# advsensor.net
KiCad netlist of a schematic drawn in Altium Designer
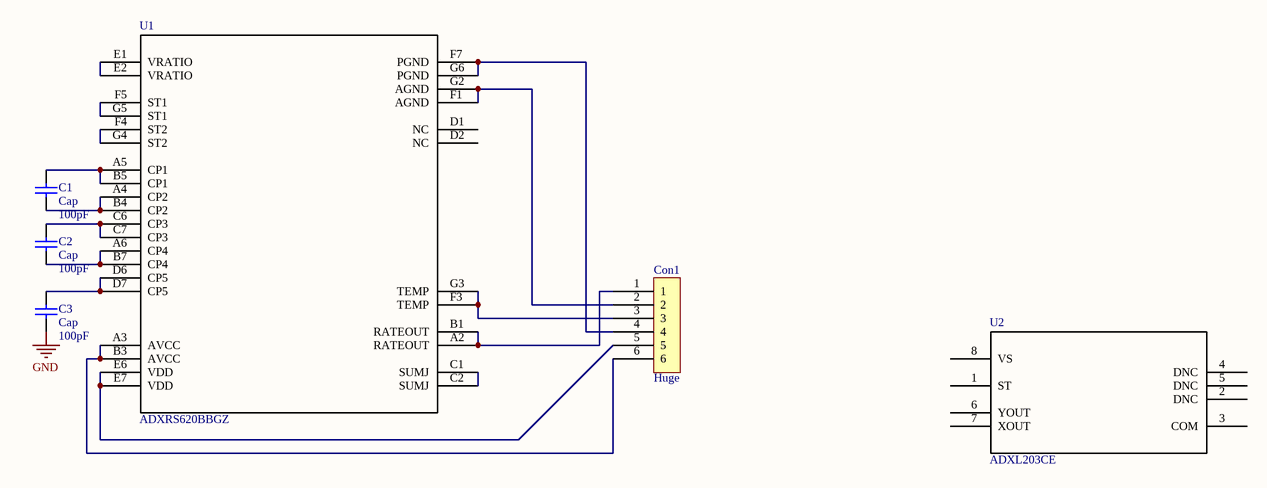
[diagram p0: advsensor.SchDoc]

(export (version "E")
  (design (tool "Eeschema 10.0.6"))
  (components
    (comp (ref "C1")
      (value "Cap")
      (footprint "0805")
      (description "Capacitor")
      (fields (field (name "ALTIUM_VALUE") "100pF") (field (name "PUBLISHER") "Altium Limited"))
      (libsource (lib "Miscellaneous Devices") (part "Cap"))
    )
    (comp (ref "C2")
      (value "Cap")
      (footprint "0805")
      (description "Capacitor")
      (fields (field (name "ALTIUM_VALUE") "100pF") (field (name "PUBLISHER") "Altium Limited"))
      (libsource (lib "Miscellaneous Devices") (part "Cap"))
    )
    (comp (ref "C3")
      (value "Cap")
      (footprint "0805")
      (description "Capacitor")
      (fields (field (name "ALTIUM_VALUE") "100pF") (field (name "PUBLISHER") "Altium Limited"))
      (libsource (lib "Miscellaneous Devices") (part "Cap"))
    )
    (comp (ref "Con1") (value "Huge") (footprint "HUGE2") (libsource (lib "complements") (part "Huge")))
    (comp (ref "U1")
      (value "ADXRS620BBGZ")
      (footprint "BG_32_3")
      (description "Imported")
      (fields (field (name "MANUFACTURER_PART_NUMBER") "ADXRS613BBGZ"))
      (libsource (lib "complements") (part "ADXRS620BBGZ"))
    )
    (comp (ref "U2")
      (value "ADXL203CE")
      (footprint "ADXL203")
      (description "Imported")
      (libsource (lib "complements") (part "ADXL203CE"))
    )
  )
  (nets
    (net (code "1") (name "GND") (class "Default")
      (node (ref "C3") (pin "1") (pinfunction "1_1") (pintype "passive"))
    )
    (net (code "2") (name "Net-(C1-Pad1)") (class "Default")
      (node (ref "C1") (pin "1") (pinfunction "1_1") (pintype "passive"))
      (node (ref "U1") (pin "A4") (pinfunction "CP2_A4") (pintype "passive"))
      (node (ref "U1") (pin "B4") (pinfunction "CP2_B4") (pintype "passive"))
    )
    (net (code "3") (name "Net-(C1-Pad2)") (class "Default")
      (node (ref "C1") (pin "2") (pinfunction "2_2") (pintype "passive"))
      (node (ref "U1") (pin "A5") (pinfunction "CP1_A5") (pintype "passive"))
      (node (ref "U1") (pin "B5") (pinfunction "CP1_B5") (pintype "passive"))
    )
    (net (code "4") (name "Net-(C2-Pad1)") (class "Default")
      (node (ref "C2") (pin "1") (pinfunction "1_1") (pintype "passive"))
      (node (ref "U1") (pin "A6") (pinfunction "CP4_A6") (pintype "passive"))
      (node (ref "U1") (pin "B7") (pinfunction "CP4_B7") (pintype "passive"))
    )
    (net (code "5") (name "Net-(C2-Pad2)") (class "Default")
      (node (ref "C2") (pin "2") (pinfunction "2_2") (pintype "passive"))
      (node (ref "U1") (pin "C6") (pinfunction "CP3_C6") (pintype "passive"))
      (node (ref "U1") (pin "C7") (pinfunction "CP3_C7") (pintype "passive"))
    )
    (net (code "6") (name "Net-(C3-Pad2)") (class "Default")
      (node (ref "C3") (pin "2") (pinfunction "2_2") (pintype "passive"))
      (node (ref "U1") (pin "D6") (pinfunction "CP5_D6") (pintype "passive"))
      (node (ref "U1") (pin "D7") (pinfunction "CP5_D7") (pintype "passive"))
    )
    (net (code "7") (name "Net-(Con1-Pad1)") (class "Default")
      (node (ref "Con1") (pin "1") (pinfunction "1_1") (pintype "passive"))
      (node (ref "U1") (pin "A2") (pinfunction "RATEOUT_A2") (pintype "passive"))
      (node (ref "U1") (pin "B1") (pinfunction "RATEOUT_B1") (pintype "passive"))
    )
    (net (code "8") (name "Net-(Con1-Pad2)") (class "Default")
      (node (ref "Con1") (pin "2") (pinfunction "2_2") (pintype "passive"))
      (node (ref "U1") (pin "F1") (pinfunction "AGND_F1") (pintype "passive"))
      (node (ref "U1") (pin "G2") (pinfunction "AGND_G2") (pintype "passive"))
    )
    (net (code "9") (name "Net-(Con1-Pad3)") (class "Default")
      (node (ref "Con1") (pin "3") (pinfunction "3_3") (pintype "passive"))
      (node (ref "U1") (pin "F3") (pinfunction "TEMP_F3") (pintype "passive"))
      (node (ref "U1") (pin "G3") (pinfunction "TEMP_G3") (pintype "passive"))
    )
    (net (code "10") (name "Net-(Con1-Pad4)") (class "Default")
      (node (ref "Con1") (pin "4") (pinfunction "4_4") (pintype "passive"))
      (node (ref "U1") (pin "F7") (pinfunction "PGND_F7") (pintype "passive"))
      (node (ref "U1") (pin "G6") (pinfunction "PGND_G6") (pintype "passive"))
    )
    (net (code "11") (name "Net-(Con1-Pad5)") (class "Default")
      (node (ref "Con1") (pin "5") (pinfunction "5_5") (pintype "passive"))
      (node (ref "U1") (pin "E6") (pinfunction "VDD_E6") (pintype "power_in"))
      (node (ref "U1") (pin "E7") (pinfunction "VDD_E7") (pintype "power_in"))
    )
    (net (code "12") (name "Net-(Con1-Pad6)") (class "Default")
      (node (ref "Con1") (pin "6") (pinfunction "6_6") (pintype "passive"))
      (node (ref "U1") (pin "A3") (pinfunction "AVCC_A3") (pintype "power_in"))
      (node (ref "U1") (pin "B3") (pinfunction "AVCC_B3") (pintype "power_in"))
    )
    (net (code "13") (name "Net-(U1-ST1-PadF5)") (class "Default")
      (node (ref "U1") (pin "F5") (pinfunction "ST1_F5") (pintype "passive"))
      (node (ref "U1") (pin "G5") (pinfunction "ST1_G5") (pintype "passive"))
    )
    (net (code "14") (name "Net-(U1-ST2-PadF4)") (class "Default")
      (node (ref "U1") (pin "F4") (pinfunction "ST2_F4") (pintype "passive"))
      (node (ref "U1") (pin "G4") (pinfunction "ST2_G4") (pintype "passive"))
    )
    (net (code "15") (name "Net-(U1-SUMJ-PadC1)") (class "Default")
      (node (ref "U1") (pin "C1") (pinfunction "SUMJ_C1") (pintype "passive"))
      (node (ref "U1") (pin "C2") (pinfunction "SUMJ_C2") (pintype "passive"))
    )
    (net (code "16") (name "Net-(U1-VRATIO-PadE1)") (class "Default")
      (node (ref "U1") (pin "E1") (pinfunction "VRATIO_E1") (pintype "power_in"))
      (node (ref "U1") (pin "E2") (pinfunction "VRATIO_E2") (pintype "power_in"))
    )
    (net (code "17") (name "unconnected-(U1-NC-PadD1)") (class "Default")
      (node (ref "U1") (pin "D1") (pinfunction "NC_D1") (pintype "passive"))
    )
    (net (code "18") (name "unconnected-(U1-NC-PadD2)") (class "Default")
      (node (ref "U1") (pin "D2") (pinfunction "NC_D2") (pintype "passive"))
    )
    (net (code "19") (name "unconnected-(U2-COM-Pad3)") (class "Default")
      (node (ref "U2") (pin "3") (pinfunction "COM_3") (pintype "passive"))
    )
    (net (code "20") (name "unconnected-(U2-DNC-Pad2)") (class "Default")
      (node (ref "U2") (pin "2") (pinfunction "DNC_2") (pintype "passive"))
    )
    (net (code "21") (name "unconnected-(U2-DNC-Pad4)") (class "Default")
      (node (ref "U2") (pin "4") (pinfunction "DNC_4") (pintype "passive"))
    )
    (net (code "22") (name "unconnected-(U2-DNC-Pad5)") (class "Default")
      (node (ref "U2") (pin "5") (pinfunction "DNC_5") (pintype "passive"))
    )
    (net (code "23") (name "unconnected-(U2-ST-Pad1)") (class "Default")
      (node (ref "U2") (pin "1") (pinfunction "ST_1") (pintype "passive"))
    )
    (net (code "24") (name "unconnected-(U2-VS-Pad8)") (class "Default")
      (node (ref "U2") (pin "8") (pinfunction "VS_8") (pintype "passive"))
    )
    (net (code "25") (name "unconnected-(U2-XOUT-Pad7)") (class "Default")
      (node (ref "U2") (pin "7") (pinfunction "XOUT_7") (pintype "passive"))
    )
    (net (code "26") (name "unconnected-(U2-YOUT-Pad6)") (class "Default")
      (node (ref "U2") (pin "6") (pinfunction "YOUT_6") (pintype "passive"))
    )
  )
)
